# H-BRIDGE.net
KiCad netlist of a schematic drawn in Altium Designer
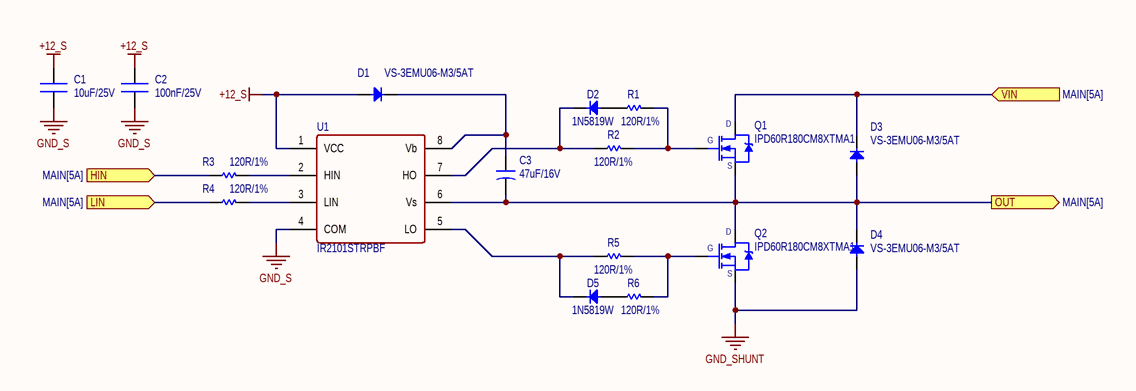
[diagram p0: H-BRIDGE.SchDoc]

(export (version "E")
  (design (tool "Eeschema 10.0.6"))
  (components
    (comp (ref "C1")
      (value "10uF/25V")
      (footprint "CN-SMD-0603")
      (description "0603W106M250XD")
      (libsource (lib "Library") (part "CN"))
    )
    (comp (ref "C2")
      (value "100nF/25V")
      (footprint "CN-SMD-0603")
      (description "CL10B104KA8NNNC")
      (libsource (lib "Library") (part "CN"))
    )
    (comp (ref "C3")
      (value "47uF/16V")
      (footprint "Tantalum 1210")
      (description "TCNT476M016R0200")
      (fields (field (name "PUBLISHER") "Altium Limited"))
      (libsource (lib "Library") (part "CN-SMD"))
    )
    (comp (ref "D1")
      (value "VS-3EMU06-M3/5AT")
      (footprint "DIO-SMD-A")
      (fields (field (name "PUBLISHER") "Altium Limited"))
      (libsource (lib "Library") (part "Diode SMD"))
    )
    (comp (ref "D2")
      (value "1N5819W")
      (footprint "DIO-SMD-123")
      (fields (field (name "PUBLISHER") "Altium Limited"))
      (libsource (lib "Library") (part "Diode SMD"))
    )
    (comp (ref "D3")
      (value "VS-3EMU06-M3/5AT")
      (footprint "DIO-SMD-A")
      (fields (field (name "PUBLISHER") "Altium Limited"))
      (libsource (lib "Library") (part "Diode SMD"))
    )
    (comp (ref "D4")
      (value "VS-3EMU06-M3/5AT")
      (footprint "DIO-SMD-A")
      (fields (field (name "PUBLISHER") "Altium Limited"))
      (libsource (lib "Library") (part "Diode SMD"))
    )
    (comp (ref "D5")
      (value "1N5819W")
      (footprint "DIO-SMD-123")
      (fields (field (name "PUBLISHER") "Altium Limited"))
      (libsource (lib "Library") (part "Diode SMD"))
    )
    (comp (ref "Q1")
      (value "IPD60R180CM8XTMA1")
      (footprint "TO252-123")
      (libsource (lib "Library") (part "FDD8870"))
    )
    (comp (ref "Q2")
      (value "IPD60R180CM8XTMA1")
      (footprint "TO252-123")
      (libsource (lib "Library") (part "FDD8870"))
    )
    (comp (ref "R1")
      (value "120R/1%")
      (footprint "RES-SMD-0603")
      (description "ERJ-3EKF1200V")
      (fields
        (field (name "MANUFACTURER") "Generic Components")
        (field (name "PUBLISHER") "Altium Hobart Technology Centre")
      )
      (libsource (lib "Library") (part "Res-SMD"))
    )
    (comp (ref "R2")
      (value "120R/1%")
      (footprint "RES-SMD-0603")
      (description "ERJ-3EKF1200V")
      (fields
        (field (name "MANUFACTURER") "Generic Components")
        (field (name "PUBLISHER") "Altium Hobart Technology Centre")
      )
      (libsource (lib "Library") (part "Res-SMD"))
    )
    (comp (ref "R3")
      (value "120R/1%")
      (footprint "RES-SMD-0603")
      (description "ERJ-3EKF1200V")
      (fields
        (field (name "MANUFACTURER") "Generic Components")
        (field (name "PUBLISHER") "Altium Hobart Technology Centre")
      )
      (libsource (lib "Library") (part "Res-SMD"))
    )
    (comp (ref "R4")
      (value "120R/1%")
      (footprint "RES-SMD-0603")
      (description "ERJ-3EKF1200V")
      (fields
        (field (name "MANUFACTURER") "Generic Components")
        (field (name "PUBLISHER") "Altium Hobart Technology Centre")
      )
      (libsource (lib "Library") (part "Res-SMD"))
    )
    (comp (ref "R5")
      (value "120R/1%")
      (footprint "RES-SMD-0603")
      (description "ERJ-3EKF1200V")
      (fields
        (field (name "MANUFACTURER") "Generic Components")
        (field (name "PUBLISHER") "Altium Hobart Technology Centre")
      )
      (libsource (lib "Library") (part "Res-SMD"))
    )
    (comp (ref "R6")
      (value "120R/1%")
      (footprint "RES-SMD-0603")
      (description "ERJ-3EKF1200V")
      (fields
        (field (name "MANUFACTURER") "Generic Components")
        (field (name "PUBLISHER") "Altium Hobart Technology Centre")
      )
      (libsource (lib "Library") (part "Res-SMD"))
    )
    (comp (ref "U1") (value "IR2101STRPBF") (footprint "SO8") (libsource (lib "Library") (part "IR2101S")))
  )
  (nets
    (net (code "1") (name "+12_S") (class "Default")
      (node (ref "C1") (pin "2") (pinfunction "2_2") (pintype "passive"))
      (node (ref "C2") (pin "2") (pinfunction "2_2") (pintype "passive"))
      (node (ref "D1") (pin "1") (pinfunction "A_1") (pintype "passive"))
      (node (ref "U1") (pin "1") (pinfunction "VCC_1") (pintype "passive"))
    )
    (net (code "2") (name "/HIN") (class "Default")
      (node (ref "R3") (pin "1") (pinfunction "1_1") (pintype "passive"))
    )
    (net (code "3") (name "/LIN") (class "Default")
      (node (ref "R4") (pin "1") (pinfunction "1_1") (pintype "passive"))
    )
    (net (code "4") (name "/OUT") (class "Default")
      (node (ref "C3") (pin "2") (pinfunction "2_2") (pintype "passive"))
      (node (ref "D3") (pin "1") (pinfunction "A_1") (pintype "passive"))
      (node (ref "D4") (pin "2") (pinfunction "K_2") (pintype "passive"))
      (node (ref "Q1") (pin "3") (pinfunction "S_3") (pintype "passive"))
      (node (ref "Q2") (pin "2") (pinfunction "D_2") (pintype "passive"))
      (node (ref "U1") (pin "6") (pinfunction "Vs_6") (pintype "passive"))
    )
    (net (code "5") (name "/VIN") (class "Default")
      (node (ref "D3") (pin "2") (pinfunction "K_2") (pintype "passive"))
      (node (ref "Q1") (pin "2") (pinfunction "D_2") (pintype "passive"))
    )
    (net (code "6") (name "GND_S") (class "Default")
      (node (ref "C1") (pin "1") (pinfunction "1_1") (pintype "passive"))
      (node (ref "C2") (pin "1") (pinfunction "1_1") (pintype "passive"))
      (node (ref "U1") (pin "4") (pinfunction "COM_4") (pintype "passive"))
    )
    (net (code "7") (name "GND_SHUNT") (class "Default")
      (node (ref "D4") (pin "1") (pinfunction "A_1") (pintype "passive"))
      (node (ref "Q2") (pin "3") (pinfunction "S_3") (pintype "passive"))
    )
    (net (code "8") (name "Net-(D1-K)") (class "Default")
      (node (ref "C3") (pin "1") (pinfunction "1_1") (pintype "passive"))
      (node (ref "D1") (pin "2") (pinfunction "K_2") (pintype "passive"))
      (node (ref "U1") (pin "8") (pinfunction "Vb_8") (pintype "passive"))
    )
    (net (code "9") (name "Net-(D2-A)") (class "Default")
      (node (ref "D2") (pin "1") (pinfunction "A_1") (pintype "passive"))
      (node (ref "R1") (pin "1") (pinfunction "1_1") (pintype "passive"))
    )
    (net (code "10") (name "Net-(D2-K)") (class "Default")
      (node (ref "D2") (pin "2") (pinfunction "K_2") (pintype "passive"))
      (node (ref "R2") (pin "1") (pinfunction "1_1") (pintype "passive"))
      (node (ref "U1") (pin "7") (pinfunction "HO_7") (pintype "passive"))
    )
    (net (code "11") (name "Net-(D5-A)") (class "Default")
      (node (ref "D5") (pin "1") (pinfunction "A_1") (pintype "passive"))
      (node (ref "R6") (pin "1") (pinfunction "1_1") (pintype "passive"))
    )
    (net (code "12") (name "Net-(D5-K)") (class "Default")
      (node (ref "D5") (pin "2") (pinfunction "K_2") (pintype "passive"))
      (node (ref "R5") (pin "1") (pinfunction "1_1") (pintype "passive"))
      (node (ref "U1") (pin "5") (pinfunction "LO_5") (pintype "passive"))
    )
    (net (code "13") (name "Net-(Q1-G)") (class "Default")
      (node (ref "Q1") (pin "1") (pinfunction "G_1") (pintype "passive"))
      (node (ref "R1") (pin "2") (pinfunction "2_2") (pintype "passive"))
      (node (ref "R2") (pin "2") (pinfunction "2_2") (pintype "passive"))
    )
    (net (code "14") (name "Net-(Q2-G)") (class "Default")
      (node (ref "Q2") (pin "1") (pinfunction "G_1") (pintype "passive"))
      (node (ref "R5") (pin "2") (pinfunction "2_2") (pintype "passive"))
      (node (ref "R6") (pin "2") (pinfunction "2_2") (pintype "passive"))
    )
    (net (code "15") (name "Net-(U1-HIN)") (class "Default")
      (node (ref "R3") (pin "2") (pinfunction "2_2") (pintype "passive"))
      (node (ref "U1") (pin "2") (pinfunction "HIN_2") (pintype "passive"))
    )
    (net (code "16") (name "Net-(U1-LIN)") (class "Default")
      (node (ref "R4") (pin "2") (pinfunction "2_2") (pintype "passive"))
      (node (ref "U1") (pin "3") (pinfunction "LIN_3") (pintype "passive"))
    )
  )
)
